# XPanelNew.net
KiCad netlist of a schematic drawn in EAGLE
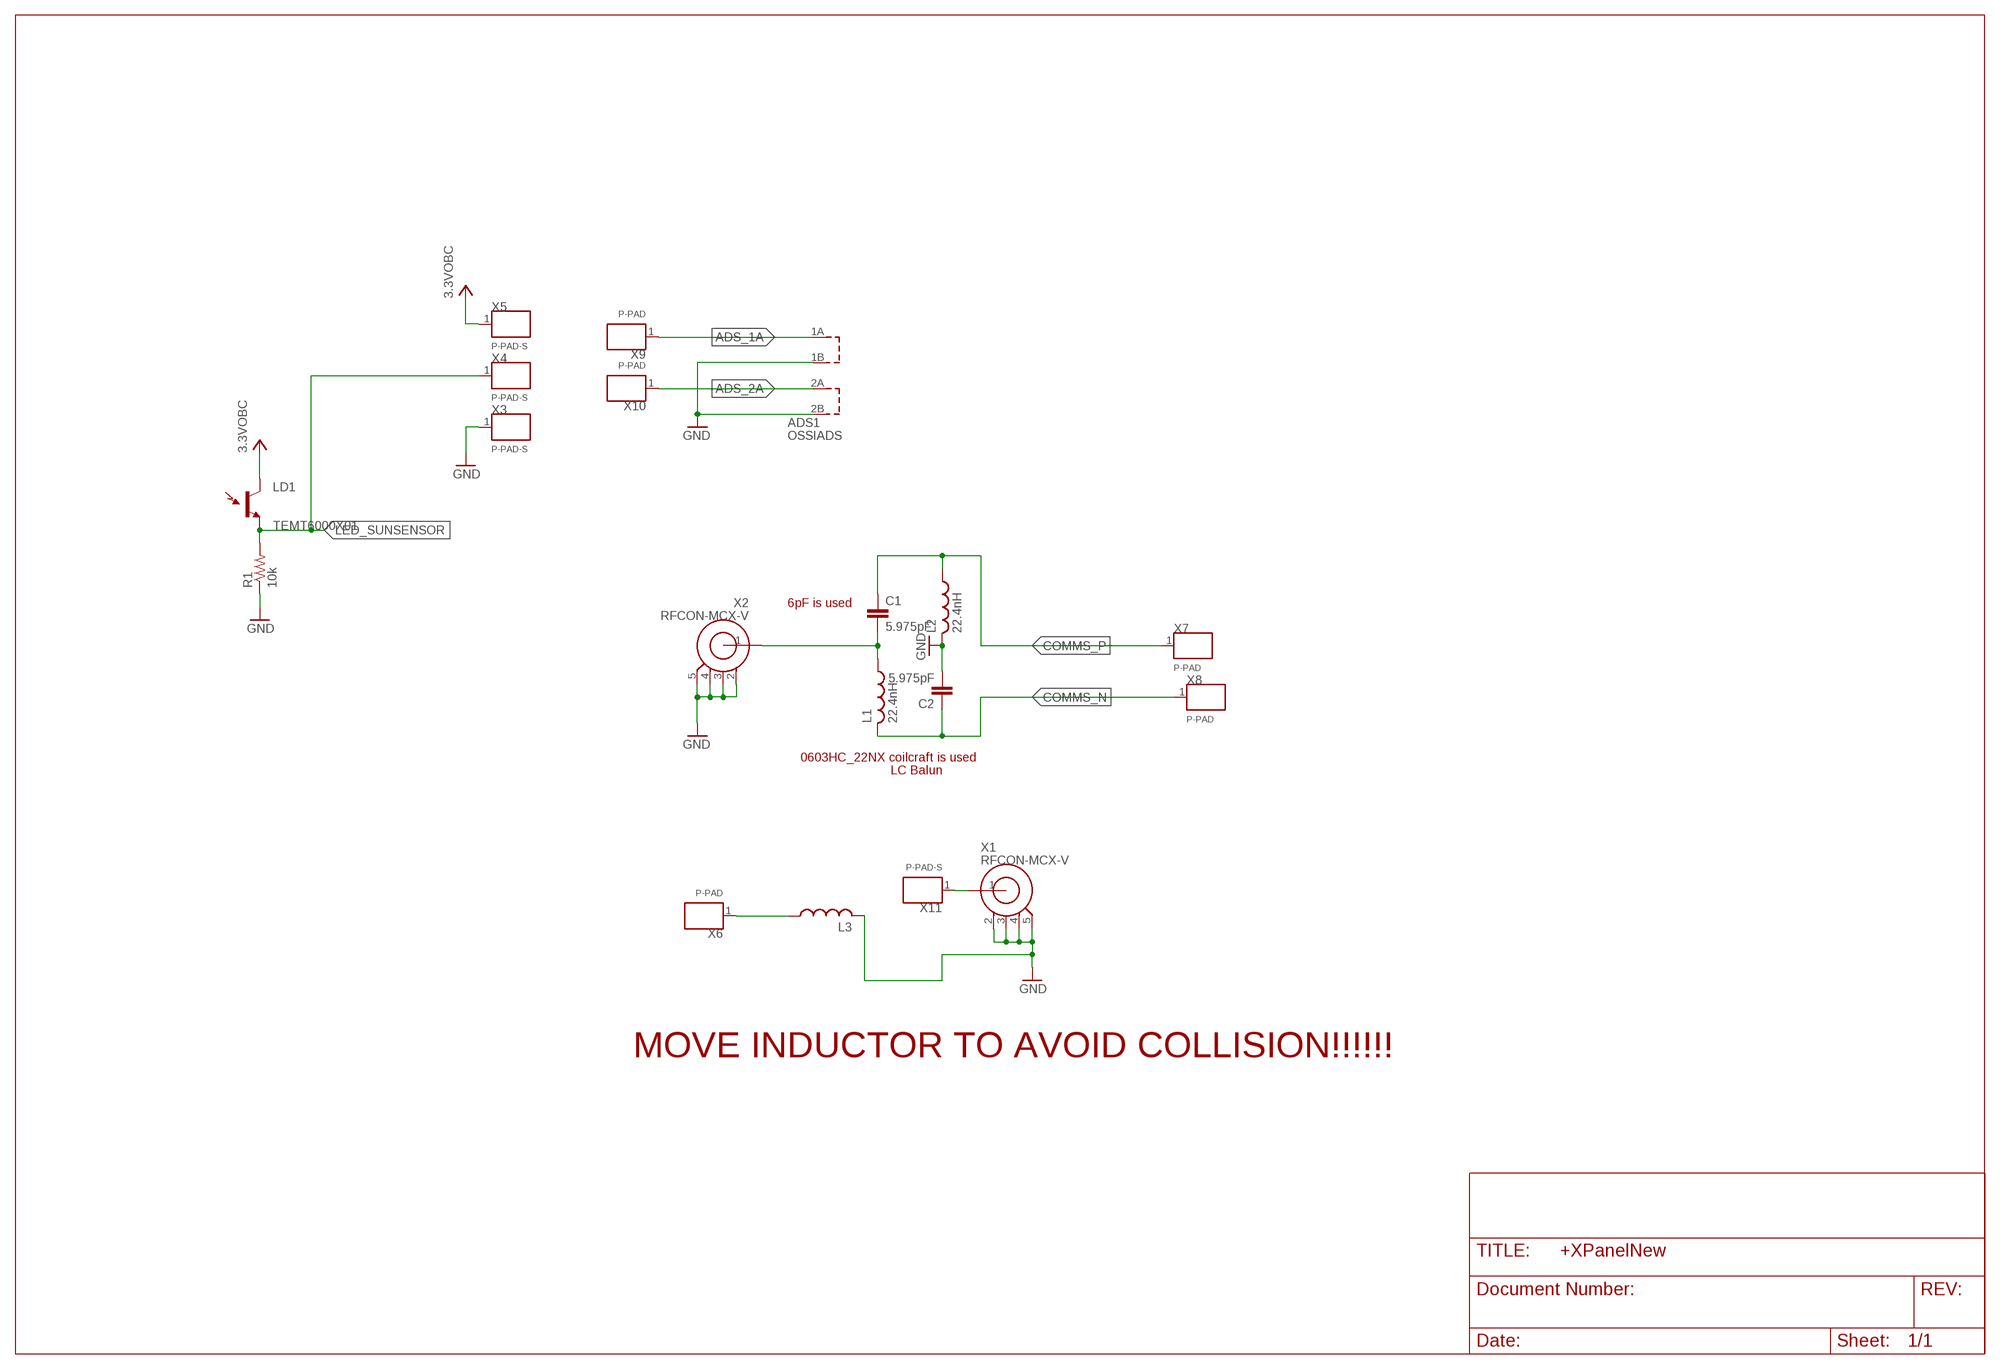
[diagram p0: schematic, sheet 1]

(export (version "E")
  (design (tool "Eeschema 10.0.6"))
  (components
    (comp (ref "ADS1")
      (value "OSSIADS")
      (footprint "eagle-import:OSSIADS")
      (libsource (lib "eagle-import") (part "OSSIADS"))
    )
    (comp (ref "C1")
      (value "5.975pF")
      (footprint "eagle-import:C0805(2012)")
      (libsource (lib "eagle-import") (part "C0805(2012)"))
    )
    (comp (ref "C2")
      (value "5.975pF")
      (footprint "eagle-import:C0805(2012)")
      (libsource (lib "eagle-import") (part "C0805(2012)"))
    )
    (comp (ref "L1")
      (value "22.4nH")
      (footprint "eagle-import:L0805(2012)")
      (libsource (lib "eagle-import") (part "L0805(2012)"))
    )
    (comp (ref "L2")
      (value "22.4nH")
      (footprint "eagle-import:L0805(2012)")
      (libsource (lib "eagle-import") (part "L0805(2012)"))
    )
    (comp (ref "L3")
      (value "L-US0207/10")
      (footprint "eagle-import:0207_10")
      (libsource (lib "eagle-import") (part "L-US0207/10"))
    )
    (comp (ref "LD1")
      (value "TEMT6000X01")
      (footprint "eagle-import:TEMT6000-SEN")
      (libsource (lib "eagle-import") (part "TEMT6000X01"))
    )
    (comp (ref "R1")
      (value "10k")
      (footprint "eagle-import:R0805(2012)")
      (libsource (lib "eagle-import") (part "R0805(2012)"))
    )
    (comp (ref "X1")
      (value "RFCON-MCX-V")
      (footprint "eagle-import:MCX-V")
      (libsource (lib "eagle-import") (part "RFCON-MCX-V"))
    )
    (comp (ref "X2")
      (value "RFCON-MCX-V")
      (footprint "eagle-import:MCX-V")
      (libsource (lib "eagle-import") (part "RFCON-MCX-V"))
    )
    (comp (ref "X3")
      (value "P-PAD-S")
      (footprint "eagle-import:P-PAD-S")
      (libsource (lib "eagle-import") (part "P-PAD-S"))
    )
    (comp (ref "X4")
      (value "P-PAD-S")
      (footprint "eagle-import:P-PAD-S")
      (libsource (lib "eagle-import") (part "P-PAD-S"))
    )
    (comp (ref "X5")
      (value "P-PAD-S")
      (footprint "eagle-import:P-PAD-S")
      (libsource (lib "eagle-import") (part "P-PAD-S"))
    )
    (comp (ref "X6")
      (value "P-PAD")
      (footprint "eagle-import:P-PAD")
      (libsource (lib "eagle-import") (part "P-PAD"))
    )
    (comp (ref "X7")
      (value "P-PAD")
      (footprint "eagle-import:P-PAD")
      (libsource (lib "eagle-import") (part "P-PAD"))
    )
    (comp (ref "X8")
      (value "P-PAD")
      (footprint "eagle-import:P-PAD")
      (libsource (lib "eagle-import") (part "P-PAD"))
    )
    (comp (ref "X9")
      (value "P-PAD")
      (footprint "eagle-import:P-PAD")
      (libsource (lib "eagle-import") (part "P-PAD"))
    )
    (comp (ref "X10")
      (value "P-PAD")
      (footprint "eagle-import:P-PAD")
      (libsource (lib "eagle-import") (part "P-PAD"))
    )
    (comp (ref "X11")
      (value "P-PAD-S")
      (footprint "eagle-import:P-PAD-S")
      (libsource (lib "eagle-import") (part "P-PAD-S"))
    )
  )
  (nets
    (net (code "1") (name "3.3VOBC") (class "Default")
      (node (ref "LD1") (pin "COLLECTOR") (pinfunction "C1_COLLECTOR") (pintype "passive"))
      (node (ref "X5") (pin "1") (pinfunction "P$1_1") (pintype "bidirectional"))
    )
    (net (code "2") (name "ADS_1A") (class "Default")
      (node (ref "ADS1") (pin "1A") (pinfunction "1A_1A") (pintype "passive"))
      (node (ref "X9") (pin "1") (pinfunction "P$1_1") (pintype "bidirectional"))
    )
    (net (code "3") (name "ADS_2A") (class "Default")
      (node (ref "ADS1") (pin "2A") (pinfunction "2A_2A") (pintype "passive"))
      (node (ref "X10") (pin "1") (pinfunction "P$1_1") (pintype "bidirectional"))
    )
    (net (code "4") (name "COMMS_N") (class "Default")
      (node (ref "C2") (pin "1") (pinfunction "1_1") (pintype "passive"))
      (node (ref "L1") (pin "2") (pinfunction "2_2") (pintype "passive"))
      (node (ref "X8") (pin "1") (pinfunction "P$1_1") (pintype "bidirectional"))
    )
    (net (code "5") (name "COMMS_P") (class "Default")
      (node (ref "C1") (pin "1") (pinfunction "1_1") (pintype "passive"))
      (node (ref "L2") (pin "1") (pinfunction "1_1") (pintype "passive"))
      (node (ref "X7") (pin "1") (pinfunction "P$1_1") (pintype "bidirectional"))
    )
    (net (code "6") (name "GND") (class "Default")
      (node (ref "ADS1") (pin "1B") (pinfunction "1B_1B") (pintype "passive"))
      (node (ref "ADS1") (pin "2B") (pinfunction "2B_2B") (pintype "passive"))
      (node (ref "C2") (pin "2") (pinfunction "2_2") (pintype "passive"))
      (node (ref "L2") (pin "2") (pinfunction "2_2") (pintype "passive"))
      (node (ref "L3") (pin "2") (pinfunction "2_2") (pintype "passive"))
      (node (ref "R1") (pin "1") (pinfunction "1_1") (pintype "passive"))
      (node (ref "X1") (pin "2") (pinfunction "2_2") (pintype "power_in"))
      (node (ref "X1") (pin "3") (pinfunction "3_3") (pintype "power_in"))
      (node (ref "X1") (pin "4") (pinfunction "4_4") (pintype "power_in"))
      (node (ref "X1") (pin "5") (pinfunction "5_5") (pintype "power_in"))
      (node (ref "X2") (pin "2") (pinfunction "2_2") (pintype "power_in"))
      (node (ref "X2") (pin "3") (pinfunction "3_3") (pintype "power_in"))
      (node (ref "X2") (pin "4") (pinfunction "4_4") (pintype "power_in"))
      (node (ref "X2") (pin "5") (pinfunction "5_5") (pintype "power_in"))
      (node (ref "X3") (pin "1") (pinfunction "P$1_1") (pintype "bidirectional"))
    )
    (net (code "7") (name "LED_SUNSENSOR") (class "Default")
      (node (ref "LD1") (pin "EMITTER") (pinfunction "E1_EMITTER") (pintype "passive"))
      (node (ref "R1") (pin "2") (pinfunction "2_2") (pintype "passive"))
      (node (ref "X4") (pin "1") (pinfunction "P$1_1") (pintype "bidirectional"))
    )
    (net (code "8") (name "Net-(C1-Pad2)") (class "Default")
      (node (ref "C1") (pin "2") (pinfunction "2_2") (pintype "passive"))
      (node (ref "L1") (pin "1") (pinfunction "1_1") (pintype "passive"))
      (node (ref "X2") (pin "1") (pinfunction "1_1") (pintype "bidirectional"))
    )
    (net (code "9") (name "Net-(X6-P$1)") (class "Default")
      (node (ref "L3") (pin "1") (pinfunction "1_1") (pintype "passive"))
      (node (ref "X6") (pin "1") (pinfunction "P$1_1") (pintype "bidirectional"))
    )
    (net (code "10") (name "Net-(X11-P$1)") (class "Default")
      (node (ref "X1") (pin "1") (pinfunction "1_1") (pintype "bidirectional"))
      (node (ref "X11") (pin "1") (pinfunction "P$1_1") (pintype "bidirectional"))
    )
  )
)
